# PLCC32_programmer.net
KiCad netlist of a schematic drawn in EAGLE
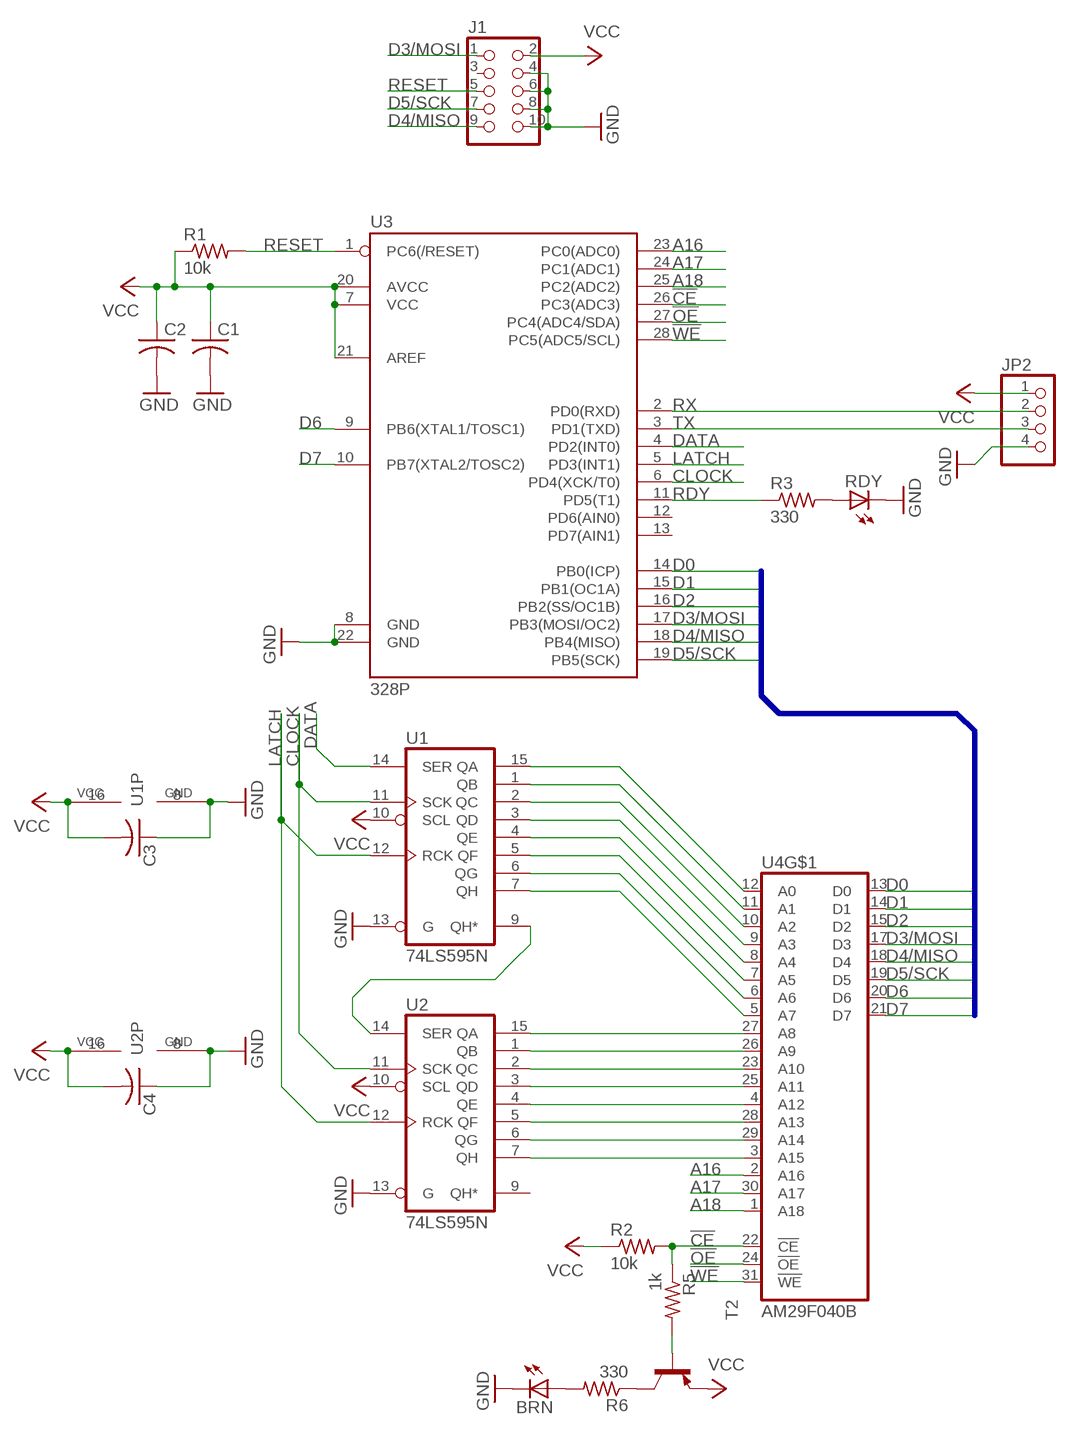
[diagram p0: schematic, sheet 1]

(export (version "E")
  (design (tool "Eeschema 10.0.6"))
  (components
    (comp (ref "BRN")
      (value "LED5MM")
      (footprint "eagle-import:LED5MM")
      (libsource (lib "eagle-import") (part "LED5MM"))
    )
    (comp (ref "C1")
      (value "C-US025-024X044")
      (footprint "eagle-import:C025-024X044")
      (libsource (lib "eagle-import") (part "C-US025-024X044"))
    )
    (comp (ref "C2")
      (value "C-US025-024X044")
      (footprint "eagle-import:C025-024X044")
      (libsource (lib "eagle-import") (part "C-US025-024X044"))
    )
    (comp (ref "C3")
      (value "C-US025-024X044")
      (footprint "eagle-import:C025-024X044")
      (libsource (lib "eagle-import") (part "C-US025-024X044"))
    )
    (comp (ref "C4")
      (value "C-US025-024X044")
      (footprint "eagle-import:C025-024X044")
      (libsource (lib "eagle-import") (part "C-US025-024X044"))
    )
    (comp (ref "J1")
      (value "CON_HEADER_2X05-PTH+SHROUDED_A")
      (footprint "eagle-import:PINSHRD_PTH_2X05")
      (libsource (lib "eagle-import") (part "CON_HEADER_2X05-PTH+SHROUDED_A"))
    )
    (comp (ref "JP2")
      (value "PINHD-1X4/OCT")
      (footprint "eagle-import:1X04_OCT")
      (libsource (lib "eagle-import") (part "PINHD-1X4/OCT"))
    )
    (comp (ref "R1")
      (value "10k")
      (footprint "eagle-import:0204_7")
      (libsource (lib "eagle-import") (part "R-US_0204/7"))
    )
    (comp (ref "R2")
      (value "10k")
      (footprint "eagle-import:0204_7")
      (libsource (lib "eagle-import") (part "R-US_0204/7"))
    )
    (comp (ref "R3")
      (value "330")
      (footprint "eagle-import:0204_7")
      (libsource (lib "eagle-import") (part "R-US_0204/7"))
    )
    (comp (ref "R5")
      (value "1k")
      (footprint "eagle-import:0204_7")
      (libsource (lib "eagle-import") (part "R-US_0204/7"))
    )
    (comp (ref "R6")
      (value "330")
      (footprint "eagle-import:0204_7")
      (libsource (lib "eagle-import") (part "R-US_0204/7"))
    )
    (comp (ref "RDY")
      (value "LED5MM")
      (footprint "eagle-import:LED5MM")
      (libsource (lib "eagle-import") (part "LED5MM"))
    )
    (comp (ref "T2")
      (value "BC558A-PNP-TO92-EBC")
      (footprint "eagle-import:TO92-EBC")
      (libsource (lib "eagle-import") (part "-PNP-TO92-EBCBC558A"))
    )
    (comp (ref "U1")
      (value "74LS595N")
      (footprint "eagle-import:DIL16")
      (fields (field (name "SPICEPREFIX") "X"))
      (libsource (lib "eagle-import") (part "74595NLS"))
    )
    (comp (ref "U2")
      (value "74LS595N")
      (footprint "eagle-import:DIL16")
      (libsource (lib "eagle-import") (part "74595NLS"))
    )
    (comp (ref "U3")
      (value "328P")
      (footprint "eagle-import:DIP28")
      (libsource (lib "eagle-import") (part "ATMEGA328P_PDIP"))
    )
    (comp (ref "U4")
      (value "AM29F040B")
      (footprint "eagle-import:PLCC-32-SMT-TT")
      (libsource (lib "eagle-import") (part "AM29F040B"))
    )
  )
  (nets
    (net (code "1") (name "/A16") (class "Default")
      (node (ref "U3") (pin "23") (pinfunction "PC0(ADC0)_23") (pintype "bidirectional"))
      (node (ref "U4") (pin "2") (pinfunction "A16_2") (pintype "input"))
    )
    (net (code "2") (name "/A17") (class "Default")
      (node (ref "U3") (pin "24") (pinfunction "PC1(ADC1)_24") (pintype "bidirectional"))
      (node (ref "U4") (pin "30") (pinfunction "A17_30") (pintype "input"))
    )
    (net (code "3") (name "/A18") (class "Default")
      (node (ref "U3") (pin "25") (pinfunction "PC2(ADC2)_25") (pintype "bidirectional"))
      (node (ref "U4") (pin "1") (pinfunction "A18_1") (pintype "input"))
    )
    (net (code "4") (name "/CLOCK") (class "Default")
      (node (ref "U1") (pin "11") (pinfunction "SCK_11") (pintype "input"))
      (node (ref "U2") (pin "11") (pinfunction "SCK_11") (pintype "input"))
      (node (ref "U3") (pin "6") (pinfunction "PD4(XCK/T0)_6") (pintype "bidirectional"))
    )
    (net (code "5") (name "/D0") (class "Default")
      (node (ref "U3") (pin "14") (pinfunction "PB0(ICP)_14") (pintype "bidirectional"))
      (node (ref "U4") (pin "13") (pinfunction "D0_13") (pintype "tri_state"))
    )
    (net (code "6") (name "/D1") (class "Default")
      (node (ref "U3") (pin "15") (pinfunction "PB1(OC1A)_15") (pintype "bidirectional"))
      (node (ref "U4") (pin "14") (pinfunction "D1_14") (pintype "tri_state"))
    )
    (net (code "7") (name "/D2") (class "Default")
      (node (ref "U3") (pin "16") (pinfunction "PB2(SS/OC1B)_16") (pintype "bidirectional"))
      (node (ref "U4") (pin "15") (pinfunction "D2_15") (pintype "tri_state"))
    )
    (net (code "8") (name "/D3{slash}MOSI") (class "Default")
      (node (ref "J1") (pin "1") (pinfunction "1_1") (pintype "passive"))
      (node (ref "U3") (pin "17") (pinfunction "PB3(MOSI/OC2)_17") (pintype "bidirectional"))
      (node (ref "U4") (pin "17") (pinfunction "D3_17") (pintype "tri_state"))
    )
    (net (code "9") (name "/D4{slash}MISO") (class "Default")
      (node (ref "J1") (pin "9") (pinfunction "9_9") (pintype "passive"))
      (node (ref "U3") (pin "18") (pinfunction "PB4(MISO)_18") (pintype "bidirectional"))
      (node (ref "U4") (pin "18") (pinfunction "D4_18") (pintype "tri_state"))
    )
    (net (code "10") (name "/D5{slash}SCK") (class "Default")
      (node (ref "J1") (pin "7") (pinfunction "7_7") (pintype "passive"))
      (node (ref "U3") (pin "19") (pinfunction "PB5(SCK)_19") (pintype "bidirectional"))
      (node (ref "U4") (pin "19") (pinfunction "D5_19") (pintype "tri_state"))
    )
    (net (code "11") (name "/D6") (class "Default")
      (node (ref "U3") (pin "9") (pinfunction "PB6(XTAL1/TOSC1)_9") (pintype "bidirectional"))
      (node (ref "U4") (pin "20") (pinfunction "D6_20") (pintype "tri_state"))
    )
    (net (code "12") (name "/D7") (class "Default")
      (node (ref "U3") (pin "10") (pinfunction "PB7(XTAL2/TOSC2)_10") (pintype "bidirectional"))
      (node (ref "U4") (pin "21") (pinfunction "D7_21") (pintype "tri_state"))
    )
    (net (code "13") (name "/DATA") (class "Default")
      (node (ref "U1") (pin "14") (pinfunction "SER_14") (pintype "input"))
      (node (ref "U3") (pin "4") (pinfunction "PD2(INT0)_4") (pintype "bidirectional"))
    )
    (net (code "14") (name "/LATCH") (class "Default")
      (node (ref "U1") (pin "12") (pinfunction "RCK_12") (pintype "input"))
      (node (ref "U2") (pin "12") (pinfunction "RCK_12") (pintype "input"))
      (node (ref "U3") (pin "5") (pinfunction "PD3(INT1)_5") (pintype "bidirectional"))
    )
    (net (code "15") (name "/RDY") (class "Default")
      (node (ref "R3") (pin "1") (pinfunction "1_1") (pintype "passive"))
      (node (ref "U3") (pin "11") (pinfunction "PD5(T1)_11") (pintype "bidirectional"))
    )
    (net (code "16") (name "/RESET") (class "Default")
      (node (ref "J1") (pin "5") (pinfunction "5_5") (pintype "passive"))
      (node (ref "R1") (pin "2") (pinfunction "2_2") (pintype "passive"))
      (node (ref "U3") (pin "1") (pinfunction "PC6(/RESET)_1") (pintype "bidirectional"))
    )
    (net (code "17") (name "/RX") (class "Default")
      (node (ref "JP2") (pin "2") (pinfunction "2_2") (pintype "passive"))
      (node (ref "U3") (pin "2") (pinfunction "PD0(RXD)_2") (pintype "bidirectional"))
    )
    (net (code "18") (name "/TX") (class "Default")
      (node (ref "JP2") (pin "3") (pinfunction "3_3") (pintype "passive"))
      (node (ref "U3") (pin "3") (pinfunction "PD1(TXD)_3") (pintype "bidirectional"))
    )
    (net (code "19") (name "/~{CE}") (class "Default")
      (node (ref "R2") (pin "2") (pinfunction "2_2") (pintype "passive"))
      (node (ref "R5") (pin "1") (pinfunction "1_1") (pintype "passive"))
      (node (ref "U3") (pin "26") (pinfunction "PC3(ADC3)_26") (pintype "bidirectional"))
      (node (ref "U4") (pin "22") (pinfunction "~{CE}_22") (pintype "input"))
    )
    (net (code "20") (name "/~{OE}") (class "Default")
      (node (ref "U3") (pin "27") (pinfunction "PC4(ADC4/SDA)_27") (pintype "bidirectional"))
      (node (ref "U4") (pin "24") (pinfunction "~{OE}_24") (pintype "input"))
    )
    (net (code "21") (name "/~{WE}") (class "Default")
      (node (ref "U3") (pin "28") (pinfunction "PC5(ADC5/SCL)_28") (pintype "bidirectional"))
      (node (ref "U4") (pin "31") (pinfunction "~{WE}_31") (pintype "input"))
    )
    (net (code "22") (name "GND") (class "Default")
      (node (ref "BRN") (pin "K") (pinfunction "C_K") (pintype "passive"))
      (node (ref "C1") (pin "2") (pinfunction "2_2") (pintype "passive"))
      (node (ref "C2") (pin "2") (pinfunction "2_2") (pintype "passive"))
      (node (ref "C3") (pin "1") (pinfunction "1_1") (pintype "passive"))
      (node (ref "C4") (pin "1") (pinfunction "1_1") (pintype "passive"))
      (node (ref "J1") (pin "10") (pinfunction "10_10") (pintype "passive"))
      (node (ref "J1") (pin "4") (pinfunction "4_4") (pintype "passive"))
      (node (ref "J1") (pin "6") (pinfunction "6_6") (pintype "passive"))
      (node (ref "J1") (pin "8") (pinfunction "8_8") (pintype "passive"))
      (node (ref "JP2") (pin "4") (pinfunction "4_4") (pintype "passive"))
      (node (ref "RDY") (pin "K") (pinfunction "C_K") (pintype "passive"))
      (node (ref "U1") (pin "13") (pinfunction "G_13") (pintype "input"))
      (node (ref "U1") (pin "8") (pinfunction "GND_8") (pintype "power_in"))
      (node (ref "U2") (pin "13") (pinfunction "G_13") (pintype "input"))
      (node (ref "U2") (pin "8") (pinfunction "GND_8") (pintype "power_in"))
      (node (ref "U3") (pin "22") (pinfunction "GND_22") (pintype "bidirectional"))
      (node (ref "U3") (pin "8") (pinfunction "GND_8") (pintype "bidirectional"))
    )
    (net (code "23") (name "Net-(BRN-PadA)") (class "Default")
      (node (ref "BRN") (pin "A") (pinfunction "A_A") (pintype "passive"))
      (node (ref "R6") (pin "2") (pinfunction "2_2") (pintype "passive"))
    )
    (net (code "24") (name "Net-(R3-Pad2)") (class "Default")
      (node (ref "R3") (pin "2") (pinfunction "2_2") (pintype "passive"))
      (node (ref "RDY") (pin "A") (pinfunction "A_A") (pintype "passive"))
    )
    (net (code "25") (name "Net-(R5-Pad2)") (class "Default")
      (node (ref "R5") (pin "2") (pinfunction "2_2") (pintype "passive"))
      (node (ref "T2") (pin "B") (pinfunction "B_B") (pintype "passive"))
    )
    (net (code "26") (name "Net-(R6-Pad1)") (class "Default")
      (node (ref "R6") (pin "1") (pinfunction "1_1") (pintype "passive"))
      (node (ref "T2") (pin "C") (pinfunction "C_C") (pintype "passive"))
    )
    (net (code "27") (name "Net-(U1A-QA)") (class "Default")
      (node (ref "U1") (pin "15") (pinfunction "QA_15") (pintype "tri_state"))
      (node (ref "U4") (pin "12") (pinfunction "A0_12") (pintype "input"))
    )
    (net (code "28") (name "Net-(U1A-QB)") (class "Default")
      (node (ref "U1") (pin "1") (pinfunction "QB_1") (pintype "tri_state"))
      (node (ref "U4") (pin "11") (pinfunction "A1_11") (pintype "input"))
    )
    (net (code "29") (name "Net-(U1A-QC)") (class "Default")
      (node (ref "U1") (pin "2") (pinfunction "QC_2") (pintype "tri_state"))
      (node (ref "U4") (pin "10") (pinfunction "A2_10") (pintype "input"))
    )
    (net (code "30") (name "Net-(U1A-QD)") (class "Default")
      (node (ref "U1") (pin "3") (pinfunction "QD_3") (pintype "tri_state"))
      (node (ref "U4") (pin "9") (pinfunction "A3_9") (pintype "input"))
    )
    (net (code "31") (name "Net-(U1A-QE)") (class "Default")
      (node (ref "U1") (pin "4") (pinfunction "QE_4") (pintype "tri_state"))
      (node (ref "U4") (pin "8") (pinfunction "A4_8") (pintype "input"))
    )
    (net (code "32") (name "Net-(U1A-QF)") (class "Default")
      (node (ref "U1") (pin "5") (pinfunction "QF_5") (pintype "tri_state"))
      (node (ref "U4") (pin "7") (pinfunction "A5_7") (pintype "input"))
    )
    (net (code "33") (name "Net-(U1A-QG)") (class "Default")
      (node (ref "U1") (pin "6") (pinfunction "QG_6") (pintype "tri_state"))
      (node (ref "U4") (pin "6") (pinfunction "A6_6") (pintype "input"))
    )
    (net (code "34") (name "Net-(U1A-QH)") (class "Default")
      (node (ref "U1") (pin "7") (pinfunction "QH_7") (pintype "tri_state"))
      (node (ref "U4") (pin "5") (pinfunction "A7_5") (pintype "input"))
    )
    (net (code "35") (name "Net-(U1A-QH*)") (class "Default")
      (node (ref "U1") (pin "9") (pinfunction "QH*_9") (pintype "tri_state"))
      (node (ref "U2") (pin "14") (pinfunction "SER_14") (pintype "input"))
    )
    (net (code "36") (name "Net-(U2A-QA)") (class "Default")
      (node (ref "U2") (pin "15") (pinfunction "QA_15") (pintype "tri_state"))
      (node (ref "U4") (pin "27") (pinfunction "A8_27") (pintype "input"))
    )
    (net (code "37") (name "Net-(U2A-QB)") (class "Default")
      (node (ref "U2") (pin "1") (pinfunction "QB_1") (pintype "tri_state"))
      (node (ref "U4") (pin "26") (pinfunction "A9_26") (pintype "input"))
    )
    (net (code "38") (name "Net-(U2A-QC)") (class "Default")
      (node (ref "U2") (pin "2") (pinfunction "QC_2") (pintype "tri_state"))
      (node (ref "U4") (pin "23") (pinfunction "A10_23") (pintype "input"))
    )
    (net (code "39") (name "Net-(U2A-QD)") (class "Default")
      (node (ref "U2") (pin "3") (pinfunction "QD_3") (pintype "tri_state"))
      (node (ref "U4") (pin "25") (pinfunction "A11_25") (pintype "input"))
    )
    (net (code "40") (name "Net-(U2A-QE)") (class "Default")
      (node (ref "U2") (pin "4") (pinfunction "QE_4") (pintype "tri_state"))
      (node (ref "U4") (pin "4") (pinfunction "A12_4") (pintype "input"))
    )
    (net (code "41") (name "Net-(U2A-QF)") (class "Default")
      (node (ref "U2") (pin "5") (pinfunction "QF_5") (pintype "tri_state"))
      (node (ref "U4") (pin "28") (pinfunction "A13_28") (pintype "input"))
    )
    (net (code "42") (name "Net-(U2A-QG)") (class "Default")
      (node (ref "U2") (pin "6") (pinfunction "QG_6") (pintype "tri_state"))
      (node (ref "U4") (pin "29") (pinfunction "A14_29") (pintype "input"))
    )
    (net (code "43") (name "Net-(U2A-QH)") (class "Default")
      (node (ref "U2") (pin "7") (pinfunction "QH_7") (pintype "tri_state"))
      (node (ref "U4") (pin "3") (pinfunction "A15_3") (pintype "input"))
    )
    (net (code "44") (name "VCC") (class "Default")
      (node (ref "C1") (pin "1") (pinfunction "1_1") (pintype "passive"))
      (node (ref "C2") (pin "1") (pinfunction "1_1") (pintype "passive"))
      (node (ref "C3") (pin "2") (pinfunction "2_2") (pintype "passive"))
      (node (ref "C4") (pin "2") (pinfunction "2_2") (pintype "passive"))
      (node (ref "J1") (pin "2") (pinfunction "2_2") (pintype "passive"))
      (node (ref "JP2") (pin "1") (pinfunction "1_1") (pintype "passive"))
      (node (ref "R1") (pin "1") (pinfunction "1_1") (pintype "passive"))
      (node (ref "R2") (pin "1") (pinfunction "1_1") (pintype "passive"))
      (node (ref "T2") (pin "E") (pinfunction "E_E") (pintype "passive"))
      (node (ref "U1") (pin "10") (pinfunction "SCL_10") (pintype "input"))
      (node (ref "U1") (pin "16") (pinfunction "VCC_16") (pintype "power_in"))
      (node (ref "U2") (pin "10") (pinfunction "SCL_10") (pintype "input"))
      (node (ref "U2") (pin "16") (pinfunction "VCC_16") (pintype "power_in"))
      (node (ref "U3") (pin "20") (pinfunction "AVCC_20") (pintype "bidirectional"))
      (node (ref "U3") (pin "21") (pinfunction "AREF_21") (pintype "bidirectional"))
      (node (ref "U3") (pin "7") (pinfunction "VCC_7") (pintype "bidirectional"))
    )
    (net (code "45") (name "unconnected-(J1-Pad3)") (class "Default")
      (node (ref "J1") (pin "3") (pinfunction "3_3") (pintype "passive"))
    )
    (net (code "46") (name "unconnected-(U2A-QH*-Pad9)") (class "Default")
      (node (ref "U2") (pin "9") (pinfunction "QH*_9") (pintype "tri_state"))
    )
    (net (code "47") (name "unconnected-(U3-PD6(AIN0)-Pad12)") (class "Default")
      (node (ref "U3") (pin "12") (pinfunction "PD6(AIN0)_12") (pintype "bidirectional"))
    )
    (net (code "48") (name "unconnected-(U3-PD7(AIN1)-Pad13)") (class "Default")
      (node (ref "U3") (pin "13") (pinfunction "PD7(AIN1)_13") (pintype "bidirectional"))
    )
  )
)
